# H18R2_Frontend.net
KiCad netlist of a schematic drawn in Altium Designer
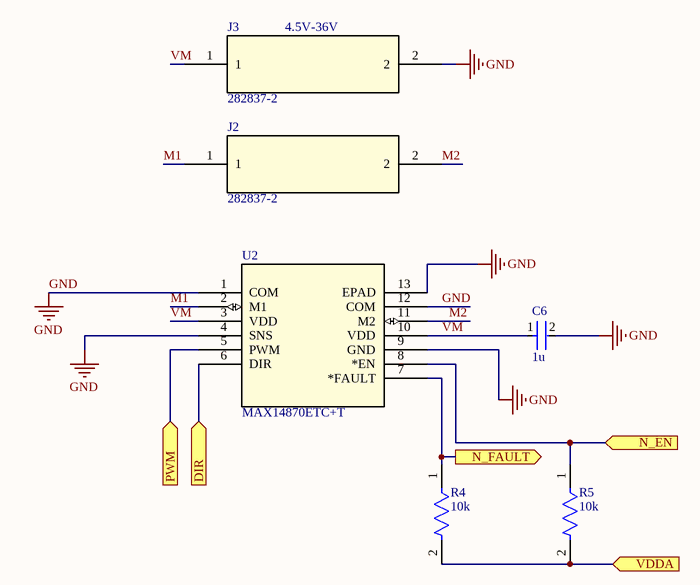
[diagram p0: H18R2_Frontend.SchDoc]

(export (version "E")
  (design (tool "Eeschema 10.0.6"))
  (components
    (comp (ref "C6")
      (value "1u")
      (footprint "FP-0603-L_1_6_0_15-W_0_8-IPC_C")
      (description "Ceramic Capacitor General Use 1uF ±10% 50V X7R 0603")
      (fields (field (name "TOLERANCE") "10%") (field (name "MANUFACTURER") "Taiyo Yuden"))
      (libsource (lib "Altium Content Vault") (part "11868f565c42a9108669ba33697ecf6"))
    )
    (comp (ref "J2")
      (value "282837-2")
      (footprint "282837-2_TYC")
      (description "TERMI-BLOK PCB MOUNT 2P")
      (fields
        (field (name "MANUFACTURER") "TE Connectivity")
        (field (name "COPYRIGHT") "Copyright (C) 2025 Ultra Librarian. All rights reserved.")
      )
      (libsource (lib "Connectors") (part "CMP-007-000000-1"))
    )
    (comp (ref "J3")
      (value "282837-2")
      (footprint "282837-2_TYC")
      (description "TERMI-BLOK PCB MOUNT 2P")
      (fields
        (field (name "MANUFACTURER") "TE Connectivity")
        (field (name "COPYRIGHT") "Copyright (C) 2025 Ultra Librarian. All rights reserved.")
      )
      (libsource (lib "Connectors") (part "CMP-007-000000-1"))
    )
    (comp (ref "R4")
      (value "10k")
      (footprint "FP-SG73P1J-MFG")
      (description "SG73P1JTTD1002F Res Thick Film 0603 10K Ohm 1% 0.2W(1/5W) ±100ppm/C Pad SMD Automotive T/R")
      (fields (field (name "TOLERANCE") "1%") (field (name "MANUFACTURER") "KOA Speer"))
      (libsource (lib "Altium Content Vault") (part "1029c3af85768c4190bb7ad29bc67b5"))
    )
    (comp (ref "R5")
      (value "10k")
      (footprint "FP-SG73P1J-MFG")
      (description "SG73P1JTTD1002F Res Thick Film 0603 10K Ohm 1% 0.2W(1/5W) ±100ppm/C Pad SMD Automotive T/R")
      (fields (field (name "TOLERANCE") "1%") (field (name "MANUFACTURER") "KOA Speer"))
      (libsource (lib "Altium Content Vault") (part "1029c3af85768c4190bb7ad29bc67b5"))
    )
    (comp (ref "U2")
      (value "MAX14870ETC+T")
      (footprint "21-0664B_MXM")
      (description "Compact 4.5V to 36V Full-Bridge DC Motor Drivers")
      (fields
        (field (name "MANUFACTURER") "Analog Devices / Maxim Integrated")
        (field (name "COPYRIGHT") "Copyright (C) 2025 Ultra Librarian. All rights reserved.")
      )
      (libsource (lib "ICs") (part "MAX14870ETC+T"))
    )
  )
  (nets
    (net (code "1") (name "/DIR") (class "Default")
      (node (ref "U2") (pin "6") (pinfunction "DIR_6") (pintype "passive"))
    )
    (net (code "2") (name "/M1") (class "Default")
      (node (ref "J2") (pin "1") (pinfunction "1_1") (pintype "passive"))
      (node (ref "U2") (pin "2") (pinfunction "M1_2") (pintype "bidirectional"))
    )
    (net (code "3") (name "/M2") (class "Default")
      (node (ref "J2") (pin "2") (pinfunction "2_2") (pintype "passive"))
      (node (ref "U2") (pin "11") (pinfunction "M2_11") (pintype "bidirectional"))
    )
    (net (code "4") (name "/N_EN") (class "Default")
      (node (ref "R5") (pin "1") (pinfunction "1_1") (pintype "passive"))
      (node (ref "U2") (pin "8") (pinfunction "*EN_8") (pintype "passive"))
    )
    (net (code "5") (name "/N_FAULT") (class "Default")
      (node (ref "R4") (pin "1") (pinfunction "1_1") (pintype "passive"))
      (node (ref "U2") (pin "7") (pinfunction "*FAULT_7") (pintype "passive"))
    )
    (net (code "6") (name "/PWM") (class "Default")
      (node (ref "U2") (pin "5") (pinfunction "PWM_5") (pintype "passive"))
    )
    (net (code "7") (name "/VDDA") (class "Default")
      (node (ref "R4") (pin "2") (pinfunction "2_2") (pintype "passive"))
      (node (ref "R5") (pin "2") (pinfunction "2_2") (pintype "passive"))
    )
    (net (code "8") (name "/VM") (class "Default")
      (node (ref "C6") (pin "1") (pinfunction "1_1") (pintype "passive"))
      (node (ref "J3") (pin "1") (pinfunction "1_1") (pintype "passive"))
      (node (ref "U2") (pin "10") (pinfunction "VDD_10") (pintype "power_in"))
      (node (ref "U2") (pin "3") (pinfunction "VDD_3") (pintype "power_in"))
    )
    (net (code "9") (name "GND") (class "Default")
      (node (ref "C6") (pin "2") (pinfunction "2_2") (pintype "passive"))
      (node (ref "J3") (pin "2") (pinfunction "2_2") (pintype "passive"))
      (node (ref "U2") (pin "1") (pinfunction "COM_1") (pintype "passive"))
      (node (ref "U2") (pin "12") (pinfunction "COM_12") (pintype "passive"))
      (node (ref "U2") (pin "13") (pinfunction "EPAD_13") (pintype "passive"))
      (node (ref "U2") (pin "4") (pinfunction "SNS_4") (pintype "passive"))
      (node (ref "U2") (pin "9") (pinfunction "GND_9") (pintype "power_in"))
    )
  )
)
